# BminiMO.net
KiCad netlist of a schematic drawn in EAGLE
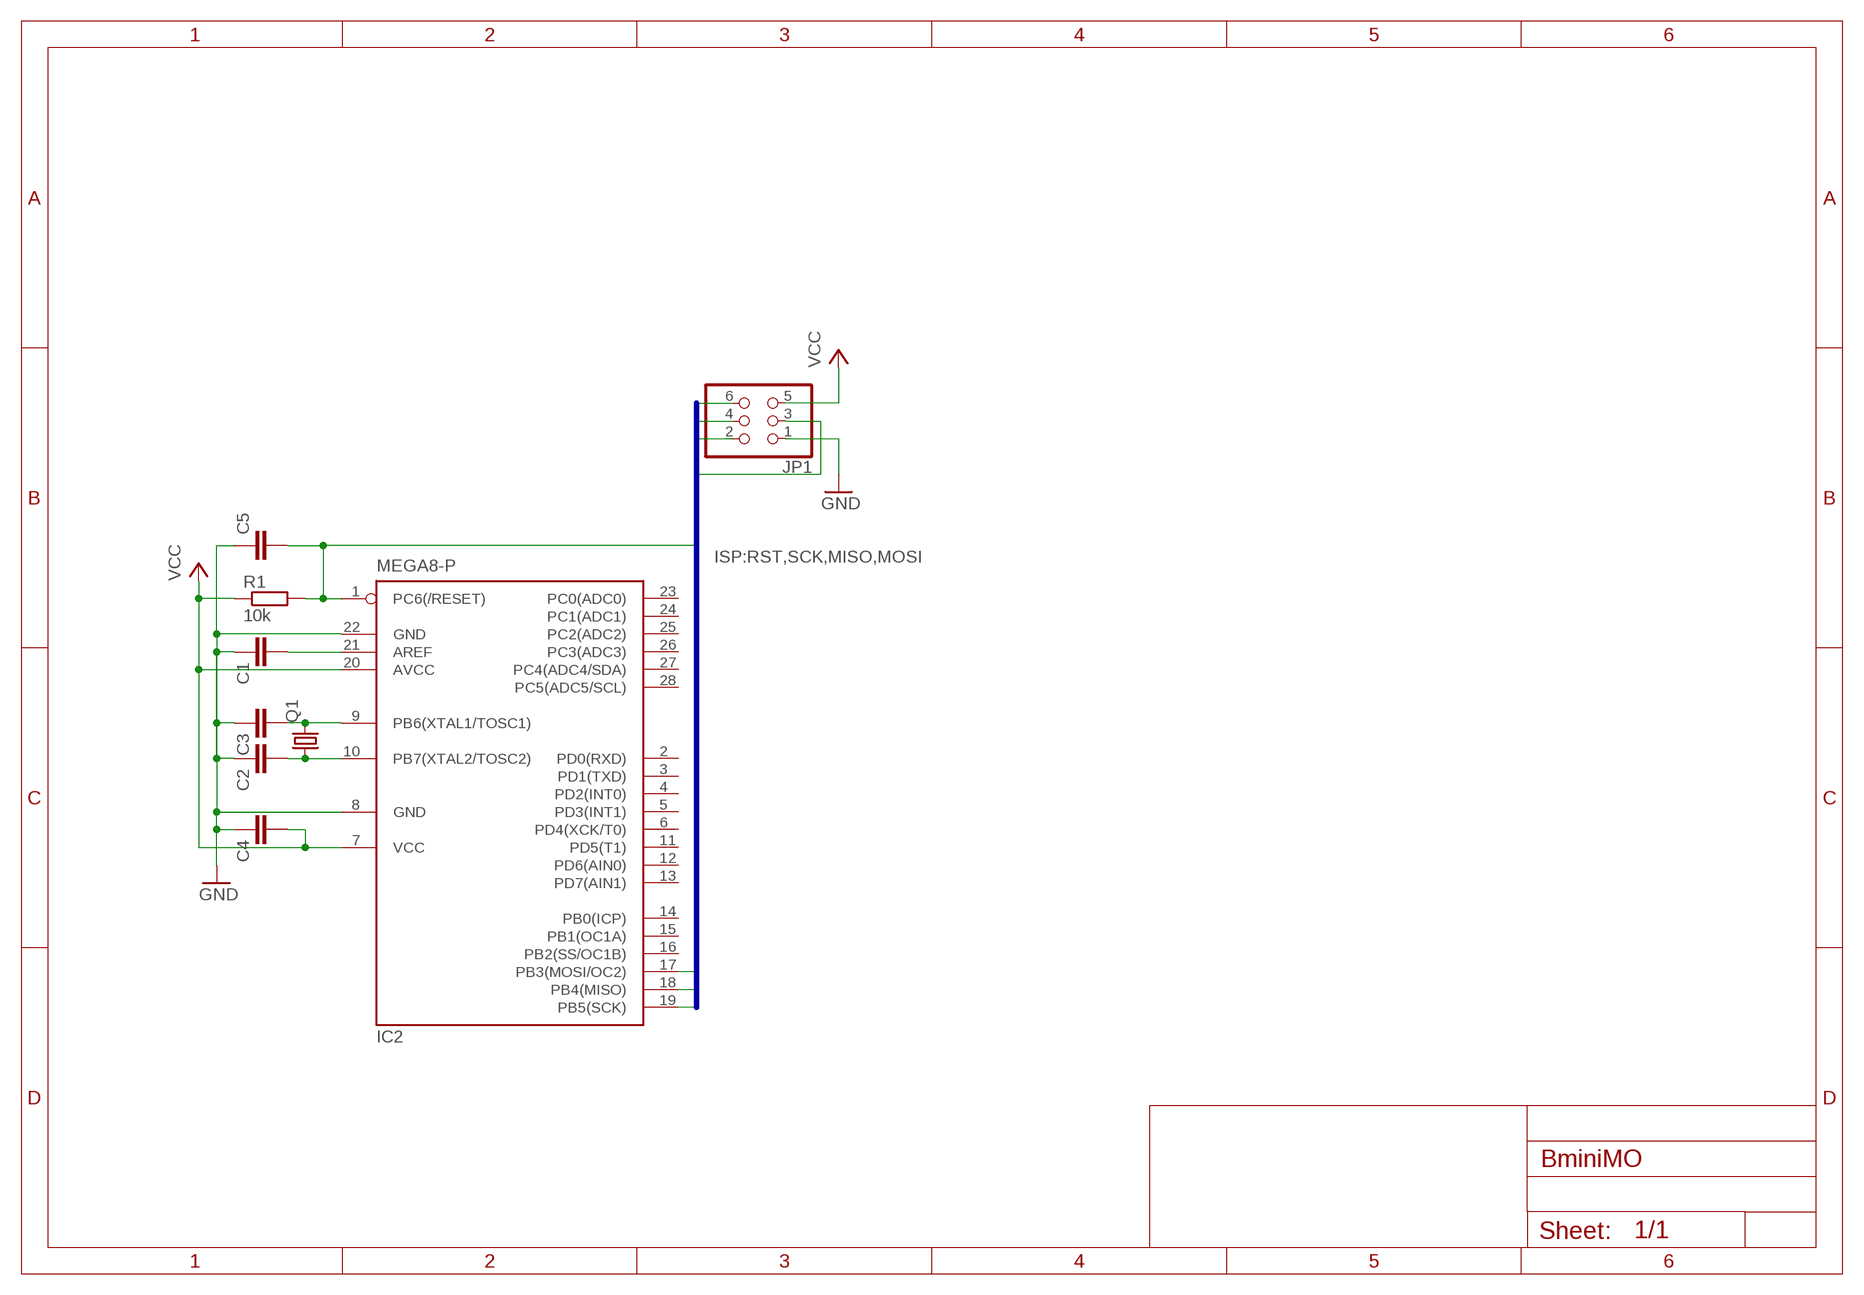
[diagram p0: schematic, sheet 1]

(export (version "E")
  (design (tool "Eeschema 10.0.6"))
  (components
    (comp (ref "C1")
      (value "C-EU025-025X050")
      (footprint "eagle-import:C025-025X050")
      (libsource (lib "eagle-import") (part "C-EU025-025X050"))
    )
    (comp (ref "C2")
      (value "C-EU025-025X050")
      (footprint "eagle-import:C025-025X050")
      (libsource (lib "eagle-import") (part "C-EU025-025X050"))
    )
    (comp (ref "C3")
      (value "C-EU025-025X050")
      (footprint "eagle-import:C025-025X050")
      (libsource (lib "eagle-import") (part "C-EU025-025X050"))
    )
    (comp (ref "C4")
      (value "C-EU025-025X050")
      (footprint "eagle-import:C025-025X050")
      (libsource (lib "eagle-import") (part "C-EU025-025X050"))
    )
    (comp (ref "C5")
      (value "C-EU025-025X050")
      (footprint "eagle-import:C025-025X050")
      (libsource (lib "eagle-import") (part "C-EU025-025X050"))
    )
    (comp (ref "IC2")
      (value "MEGA8-P")
      (footprint "eagle-import:DIL28-3")
      (libsource (lib "eagle-import") (part "MEGA8-P"))
    )
    (comp (ref "JP1")
      (value "PINHD-2X3/90")
      (footprint "eagle-import:2X03_90")
      (libsource (lib "eagle-import") (part "PINHD-2X3/90"))
    )
    (comp (ref "Q1")
      (value "CRYSTALHC49U-V")
      (footprint "eagle-import:HC49U-V")
      (libsource (lib "eagle-import") (part "CRYSTALHC49U-V"))
    )
    (comp (ref "R1")
      (value "10k")
      (footprint "eagle-import:0207_10")
      (libsource (lib "eagle-import") (part "R-EU_0207/10"))
    )
  )
  (nets
    (net (code "2") (name "/MISO") (class "Default")
      (node (ref "IC2") (pin "18") (pinfunction "PB4(MISO)_18") (pintype "bidirectional"))
      (node (ref "JP1") (pin "6") (pinfunction "6_6") (pintype "passive"))
    )
    (net (code "3") (name "/MOSI") (class "Default")
      (node (ref "IC2") (pin "17") (pinfunction "PB3(MOSI/OC2)_17") (pintype "bidirectional"))
      (node (ref "JP1") (pin "3") (pinfunction "3_3") (pintype "passive"))
    )
    (net (code "4") (name "/RST") (class "Default")
      (node (ref "C5") (pin "2") (pinfunction "2_2") (pintype "passive"))
      (node (ref "IC2") (pin "1") (pinfunction "PC6(/RESET)_1") (pintype "bidirectional"))
      (node (ref "JP1") (pin "2") (pinfunction "2_2") (pintype "passive"))
      (node (ref "R1") (pin "2") (pinfunction "2_2") (pintype "passive"))
    )
    (net (code "5") (name "/SCK") (class "Default")
      (node (ref "IC2") (pin "19") (pinfunction "PB5(SCK)_19") (pintype "bidirectional"))
      (node (ref "JP1") (pin "4") (pinfunction "4_4") (pintype "passive"))
    )
    (net (code "7") (name "GND") (class "Default")
      (node (ref "C1") (pin "1") (pinfunction "1_1") (pintype "passive"))
      (node (ref "C2") (pin "1") (pinfunction "1_1") (pintype "passive"))
      (node (ref "C3") (pin "1") (pinfunction "1_1") (pintype "passive"))
      (node (ref "C4") (pin "1") (pinfunction "1_1") (pintype "passive"))
      (node (ref "C5") (pin "1") (pinfunction "1_1") (pintype "passive"))
      (node (ref "IC2") (pin "22") (pinfunction "GND_22") (pintype "power_in"))
      (node (ref "IC2") (pin "8") (pinfunction "GND_8") (pintype "power_in"))
      (node (ref "JP1") (pin "1") (pinfunction "1_1") (pintype "passive"))
    )
    (net (code "8") (name "Net-(IC2-AREF)") (class "Default")
      (node (ref "C1") (pin "2") (pinfunction "2_2") (pintype "passive"))
      (node (ref "IC2") (pin "21") (pinfunction "AREF_21") (pintype "passive"))
    )
    (net (code "9") (name "Net-(IC2-PB6(XTAL1{slash}TOSC1))") (class "Default")
      (node (ref "C3") (pin "2") (pinfunction "2_2") (pintype "passive"))
      (node (ref "IC2") (pin "9") (pinfunction "PB6(XTAL1/TOSC1)_9") (pintype "bidirectional"))
      (node (ref "Q1") (pin "2") (pinfunction "2_2") (pintype "passive"))
    )
    (net (code "10") (name "Net-(IC2-PB7(XTAL2{slash}TOSC2))") (class "Default")
      (node (ref "C2") (pin "2") (pinfunction "2_2") (pintype "passive"))
      (node (ref "IC2") (pin "10") (pinfunction "PB7(XTAL2/TOSC2)_10") (pintype "bidirectional"))
      (node (ref "Q1") (pin "1") (pinfunction "1_1") (pintype "passive"))
    )
    (net (code "11") (name "VCC") (class "Default")
      (node (ref "C4") (pin "2") (pinfunction "2_2") (pintype "passive"))
      (node (ref "IC2") (pin "20") (pinfunction "AVCC_20") (pintype "power_in"))
      (node (ref "IC2") (pin "7") (pinfunction "VCC_7") (pintype "power_in"))
      (node (ref "JP1") (pin "5") (pinfunction "5_5") (pintype "passive"))
      (node (ref "R1") (pin "1") (pinfunction "1_1") (pintype "passive"))
    )
    (net (code "12") (name "unconnected-(IC2-PB0(ICP)-Pad14)") (class "Default")
      (node (ref "IC2") (pin "14") (pinfunction "PB0(ICP)_14") (pintype "bidirectional"))
    )
    (net (code "13") (name "unconnected-(IC2-PB1(OC1A)-Pad15)") (class "Default")
      (node (ref "IC2") (pin "15") (pinfunction "PB1(OC1A)_15") (pintype "bidirectional"))
    )
    (net (code "14") (name "unconnected-(IC2-PB2(SS{slash}OC1B)-Pad16)") (class "Default")
      (node (ref "IC2") (pin "16") (pinfunction "PB2(SS/OC1B)_16") (pintype "bidirectional"))
    )
    (net (code "15") (name "unconnected-(IC2-PC0(ADC0)-Pad23)") (class "Default")
      (node (ref "IC2") (pin "23") (pinfunction "PC0(ADC0)_23") (pintype "bidirectional"))
    )
    (net (code "16") (name "unconnected-(IC2-PC1(ADC1)-Pad24)") (class "Default")
      (node (ref "IC2") (pin "24") (pinfunction "PC1(ADC1)_24") (pintype "bidirectional"))
    )
    (net (code "17") (name "unconnected-(IC2-PC2(ADC2)-Pad25)") (class "Default")
      (node (ref "IC2") (pin "25") (pinfunction "PC2(ADC2)_25") (pintype "bidirectional"))
    )
    (net (code "18") (name "unconnected-(IC2-PC3(ADC3)-Pad26)") (class "Default")
      (node (ref "IC2") (pin "26") (pinfunction "PC3(ADC3)_26") (pintype "bidirectional"))
    )
    (net (code "19") (name "unconnected-(IC2-PC4(ADC4{slash}SDA)-Pad27)") (class "Default")
      (node (ref "IC2") (pin "27") (pinfunction "PC4(ADC4/SDA)_27") (pintype "bidirectional"))
    )
    (net (code "20") (name "unconnected-(IC2-PC5(ADC5{slash}SCL)-Pad28)") (class "Default")
      (node (ref "IC2") (pin "28") (pinfunction "PC5(ADC5/SCL)_28") (pintype "bidirectional"))
    )
    (net (code "21") (name "unconnected-(IC2-PD0(RXD)-Pad2)") (class "Default")
      (node (ref "IC2") (pin "2") (pinfunction "PD0(RXD)_2") (pintype "bidirectional"))
    )
    (net (code "22") (name "unconnected-(IC2-PD1(TXD)-Pad3)") (class "Default")
      (node (ref "IC2") (pin "3") (pinfunction "PD1(TXD)_3") (pintype "bidirectional"))
    )
    (net (code "23") (name "unconnected-(IC2-PD2(INT0)-Pad4)") (class "Default")
      (node (ref "IC2") (pin "4") (pinfunction "PD2(INT0)_4") (pintype "bidirectional"))
    )
    (net (code "24") (name "unconnected-(IC2-PD3(INT1)-Pad5)") (class "Default")
      (node (ref "IC2") (pin "5") (pinfunction "PD3(INT1)_5") (pintype "bidirectional"))
    )
    (net (code "25") (name "unconnected-(IC2-PD4(XCK{slash}T0)-Pad6)") (class "Default")
      (node (ref "IC2") (pin "6") (pinfunction "PD4(XCK/T0)_6") (pintype "bidirectional"))
    )
    (net (code "26") (name "unconnected-(IC2-PD5(T1)-Pad11)") (class "Default")
      (node (ref "IC2") (pin "11") (pinfunction "PD5(T1)_11") (pintype "bidirectional"))
    )
    (net (code "27") (name "unconnected-(IC2-PD6(AIN0)-Pad12)") (class "Default")
      (node (ref "IC2") (pin "12") (pinfunction "PD6(AIN0)_12") (pintype "bidirectional"))
    )
    (net (code "28") (name "unconnected-(IC2-PD7(AIN1)-Pad13)") (class "Default")
      (node (ref "IC2") (pin "13") (pinfunction "PD7(AIN1)_13") (pintype "bidirectional"))
    )
  )
)
